# Transmitters.net
KiCad netlist of a schematic drawn in Altium Designer
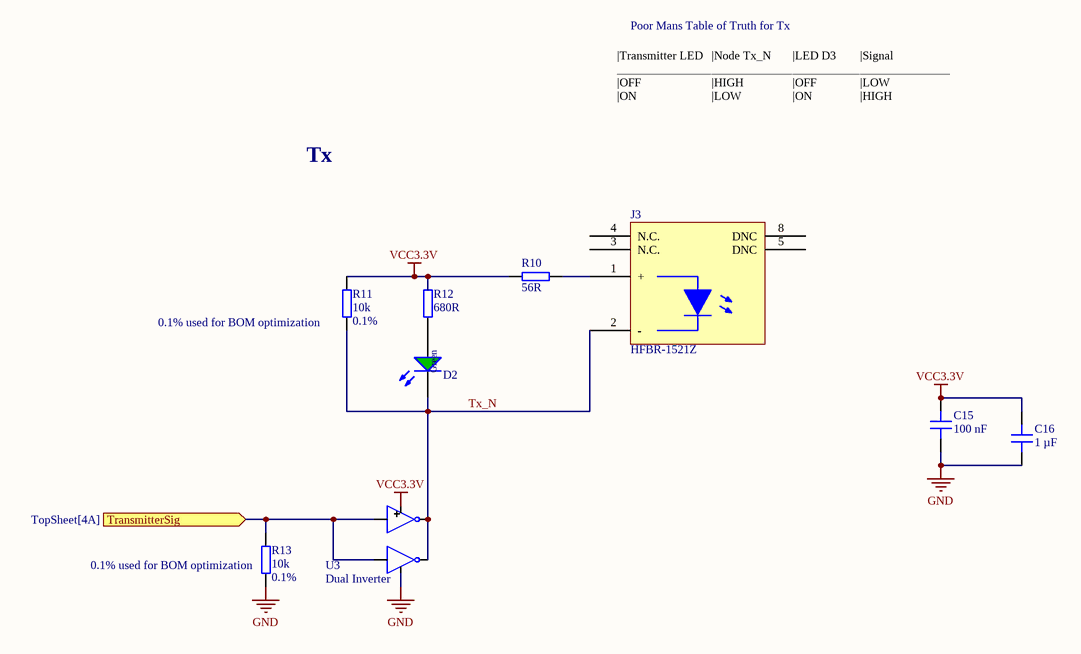
[diagram p0: Transmitters.SchDoc]

(export (version "E")
  (design (tool "Eeschema 10.0.6"))
  (components
    (comp (ref "C15")
      (value "100 nF")
      (footprint "C_0603")
      (description "Capacitor 0603, 50 VDC, 100nF, X7R")
      (fields
        (field (name "MANUFACTURER PART NUMBER") "C0603C104K5RAC3121")
        (field (name "MANUFACTURER") "KEMET")
        (field (name "CREATED FROM") "DHufnagel")
      )
      (libsource (lib "user") (part "Capacitor"))
    )
    (comp (ref "C16")
      (value "1 µF")
      (footprint "C_0603")
      (description "Capacitor 0603, 25 VDC, 1 µF, X7R")
      (fields
        (field (name "MANUFACTURER PART NUMBER") "C0603C105K3RAC7411")
        (field (name "MANUFACTURER") "KEMET")
        (field (name "CREATED FROM") "MGremer")
      )
      (libsource (lib "user") (part "Capacitor"))
    )
    (comp (ref "D2")
      (value "150060GS75000")
      (footprint "WL-SMCW_0603")
      (description "WL-SMCW SMD Mono-color Chip LED Waterclear, size 0603, Green, 3.2 V, 140°")
      (fields
        (field (name "MF") "Wuerth Elektronik")
        (field (name "LCSC PART NUMBER") "C965804")
        (field (name "CREATED") "2018_09_06_AGeiger")
      )
      (libsource (lib "UZOhm_Optical") (part "LED_Green_0603"))
    )
    (comp (ref "J3")
      (value "HFBR-1521Z")
      (footprint "HFBRx5XX")
      (description "Fibre Optic Transmitters, Link Horiz 5MBd Tx RoHS")
      (fields
        (field (name "MF") "Broadcom/Avago")
        (field (name "MANUFACTURER") "Broadcom")
        (field (name "CREATED") "2019_04_09_Kreppel")
        (field (name "CREATED FROM") "VStarost")
      )
      (libsource (lib "user") (part "HFBR-1521Z"))
    )
    (comp (ref "R10")
      (value "56R")
      (footprint "RES_2012X06N")
      (description "SMD Resistor 0805")
      (fields (field (name "MF") "Bourns") (field (name "MPN") "CR0805-FX-1200ELF"))
      (libsource (lib "UZOhm_Optical") (part "R_0805"))
    )
    (comp (ref "R11")
      (value "10k")
      (footprint "RES 0603_1608")
      (description "SMD resistor 0.1%, 10ppm")
      (fields
        (field (name "MANUFACTURER PART NUMBER") "ERA-3ARB103V")
        (field (name "MANUFACTURER") "Panasonic")
        (field (name "TOLERANCE") "0.1%")
        (field (name "CREATED FROM") "DHufnagel")
      )
      (libsource (lib "user") (part "Resistor"))
    )
    (comp (ref "R12")
      (value "680R")
      (footprint "R_0603_N")
      (description "SMD Resistor 0603")
      (fields
        (field (name "TOLERANCE") "1%")
        (field (name "VOLTAGE") "75V")
        (field (name "CREATED") "2018_09_06_AGeiger")
      )
      (libsource (lib "UZOhm_Optical") (part "R_0603"))
    )
    (comp (ref "R13")
      (value "10k")
      (footprint "RES 0603_1608")
      (description "SMD resistor 0.1%, 10ppm")
      (fields
        (field (name "MANUFACTURER PART NUMBER") "ERA-3ARB103V")
        (field (name "MANUFACTURER") "Panasonic")
        (field (name "TOLERANCE") "0.1%")
        (field (name "CREATED FROM") "DHufnagel")
      )
      (libsource (lib "user") (part "Resistor"))
    )
    (comp (ref "U3")
      (value "Dual Inverter")
      (footprint "SN74LVC2GU04DCKR")
      (description "This dual inverter is designed for 1.65-V to 5.5-V VCC\r\noperation.")
      (fields (field (name "LCSC PART NUMBER") "C116660"))
      (libsource (lib "UZOhm_Optical") (part "SN74LVC2GU04DCKR"))
    )
  )
  (nets
    (net (code "1") (name "/TransmitterSig") (class "Default")
      (node (ref "R13") (pin "1") (pinfunction "1_1") (pintype "passive"))
      (node (ref "U3") (pin "1") (pinfunction "IN1_1") (pintype "passive"))
      (node (ref "U3") (pin "3") (pinfunction "IN2_3") (pintype "passive"))
    )
    (net (code "2") (name "/Tx_N") (class "Default")
      (node (ref "D2") (pin "1") (pinfunction "K_1") (pintype "passive"))
      (node (ref "J3") (pin "2") (pinfunction "-_2") (pintype "passive"))
      (node (ref "R11") (pin "2") (pinfunction "2_2") (pintype "passive"))
      (node (ref "U3") (pin "4") (pinfunction "OUT2_4") (pintype "passive"))
      (node (ref "U3") (pin "6") (pinfunction "OUT2_6") (pintype "passive"))
    )
    (net (code "3") (name "GND") (class "Default")
      (node (ref "C15") (pin "2") (pinfunction "2_2") (pintype "passive"))
      (node (ref "C16") (pin "2") (pinfunction "2_2") (pintype "passive"))
      (node (ref "R13") (pin "2") (pinfunction "2_2") (pintype "passive"))
      (node (ref "U3") (pin "2") (pinfunction "GND_2") (pintype "passive"))
    )
    (net (code "4") (name "Net-(D2-A)") (class "Default")
      (node (ref "D2") (pin "2") (pinfunction "A_2") (pintype "passive"))
      (node (ref "R12") (pin "2") (pinfunction "2_2") (pintype "passive"))
    )
    (net (code "5") (name "Net-(J3-+)") (class "Default")
      (node (ref "J3") (pin "1") (pinfunction "+_1") (pintype "passive"))
      (node (ref "R10") (pin "2") (pintype "passive"))
    )
    (net (code "6") (name "VCC3.3V") (class "Default")
      (node (ref "C15") (pin "1") (pinfunction "1_1") (pintype "passive"))
      (node (ref "C16") (pin "1") (pinfunction "1_1") (pintype "passive"))
      (node (ref "R10") (pin "1") (pintype "passive"))
      (node (ref "R11") (pin "1") (pinfunction "1_1") (pintype "passive"))
      (node (ref "R12") (pin "1") (pinfunction "1_1") (pintype "passive"))
      (node (ref "U3") (pin "5") (pinfunction "VCC_5") (pintype "passive"))
    )
    (net (code "7") (name "unconnected-(J3-DNC-Pad5)") (class "Default")
      (node (ref "J3") (pin "5") (pinfunction "DNC_5") (pintype "passive"))
    )
    (net (code "8") (name "unconnected-(J3-DNC-Pad8)") (class "Default")
      (node (ref "J3") (pin "8") (pinfunction "DNC_8") (pintype "passive"))
    )
    (net (code "9") (name "unconnected-(J3-N.C.-Pad3)") (class "Default")
      (node (ref "J3") (pin "3") (pinfunction "N.C._3") (pintype "passive"))
    )
    (net (code "10") (name "unconnected-(J3-N.C.-Pad4)") (class "Default")
      (node (ref "J3") (pin "4") (pinfunction "N.C._4") (pintype "passive"))
    )
  )
)
